# KNOT_v1_0_main.net
KiCad netlist of a schematic drawn in EAGLE
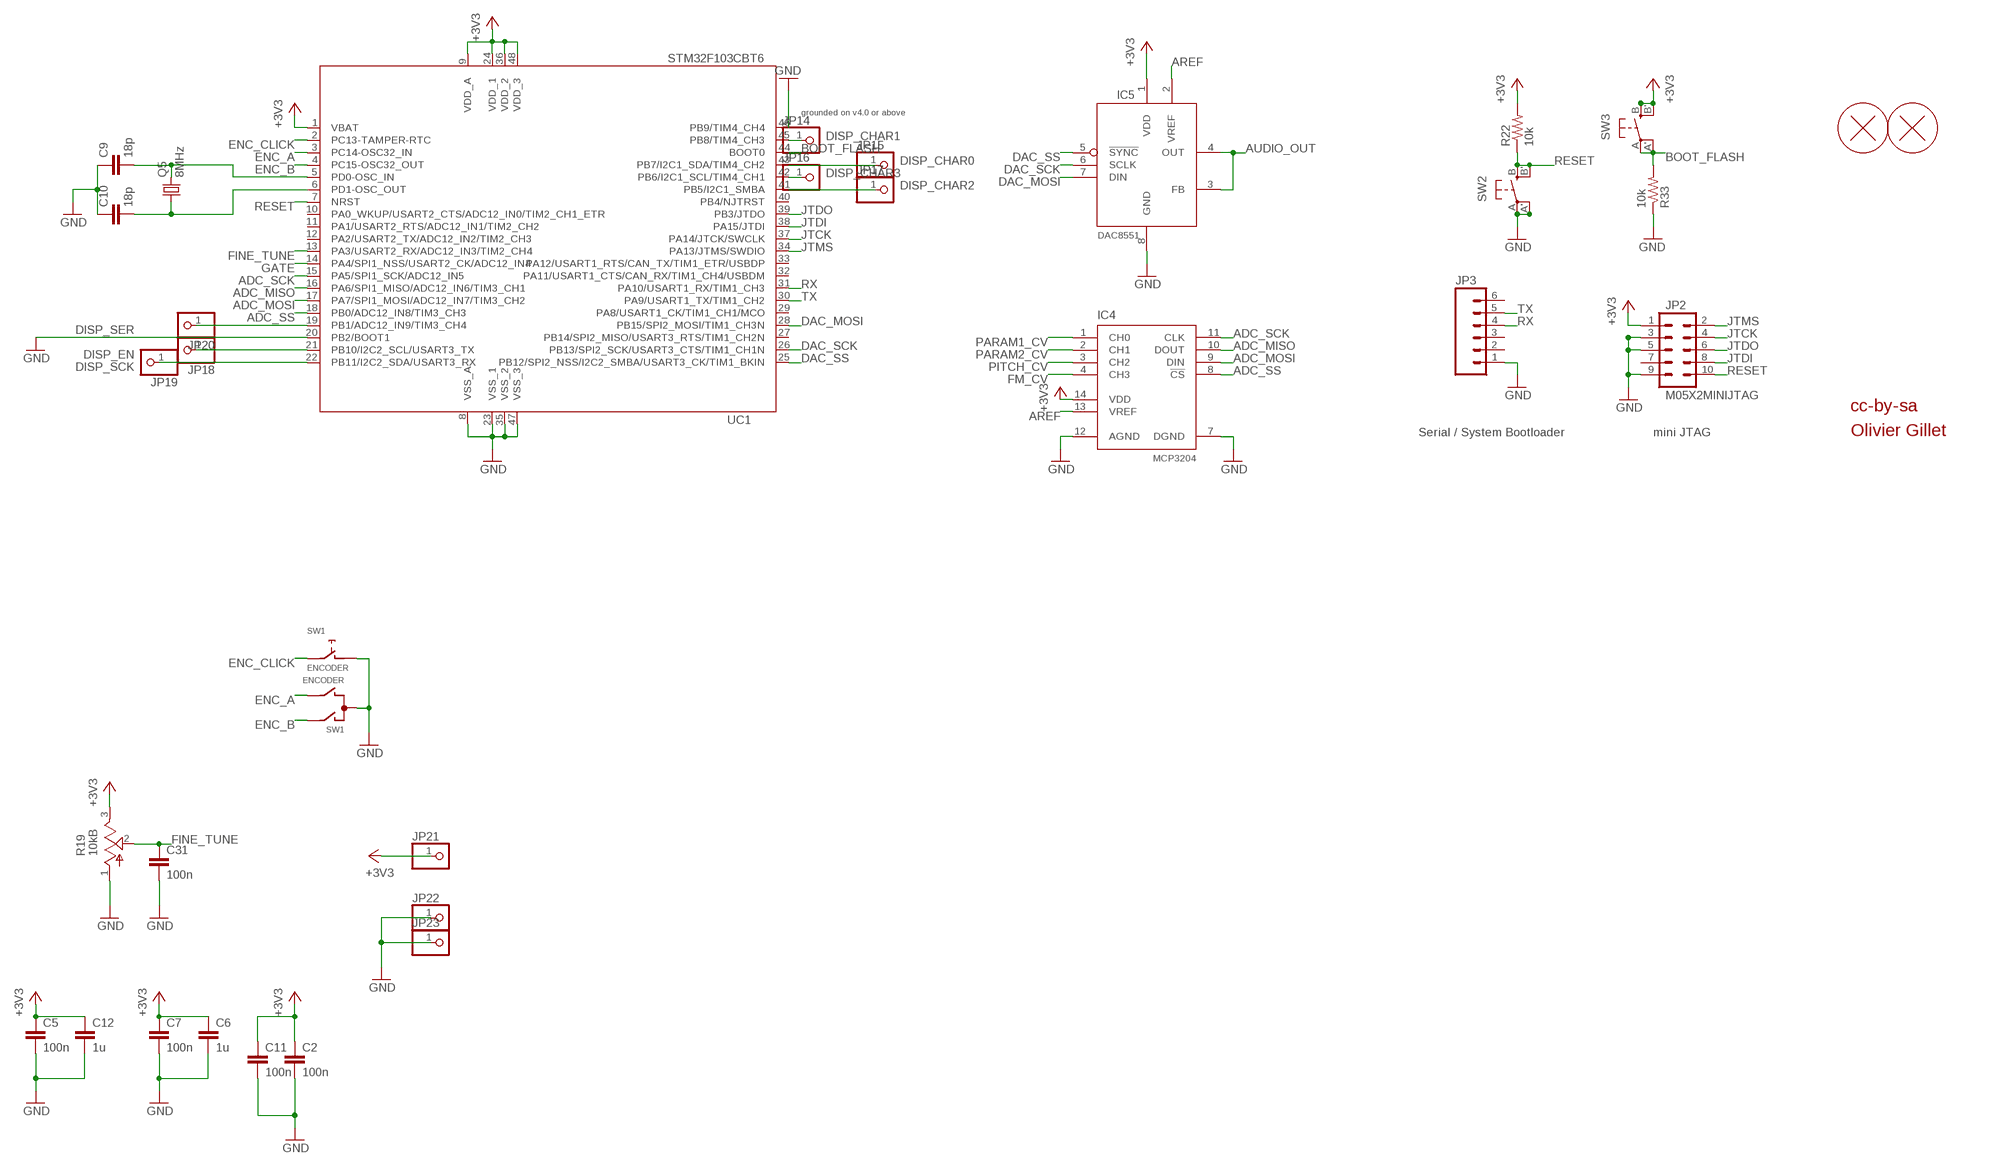
[diagram p0: schematic, sheet 1]
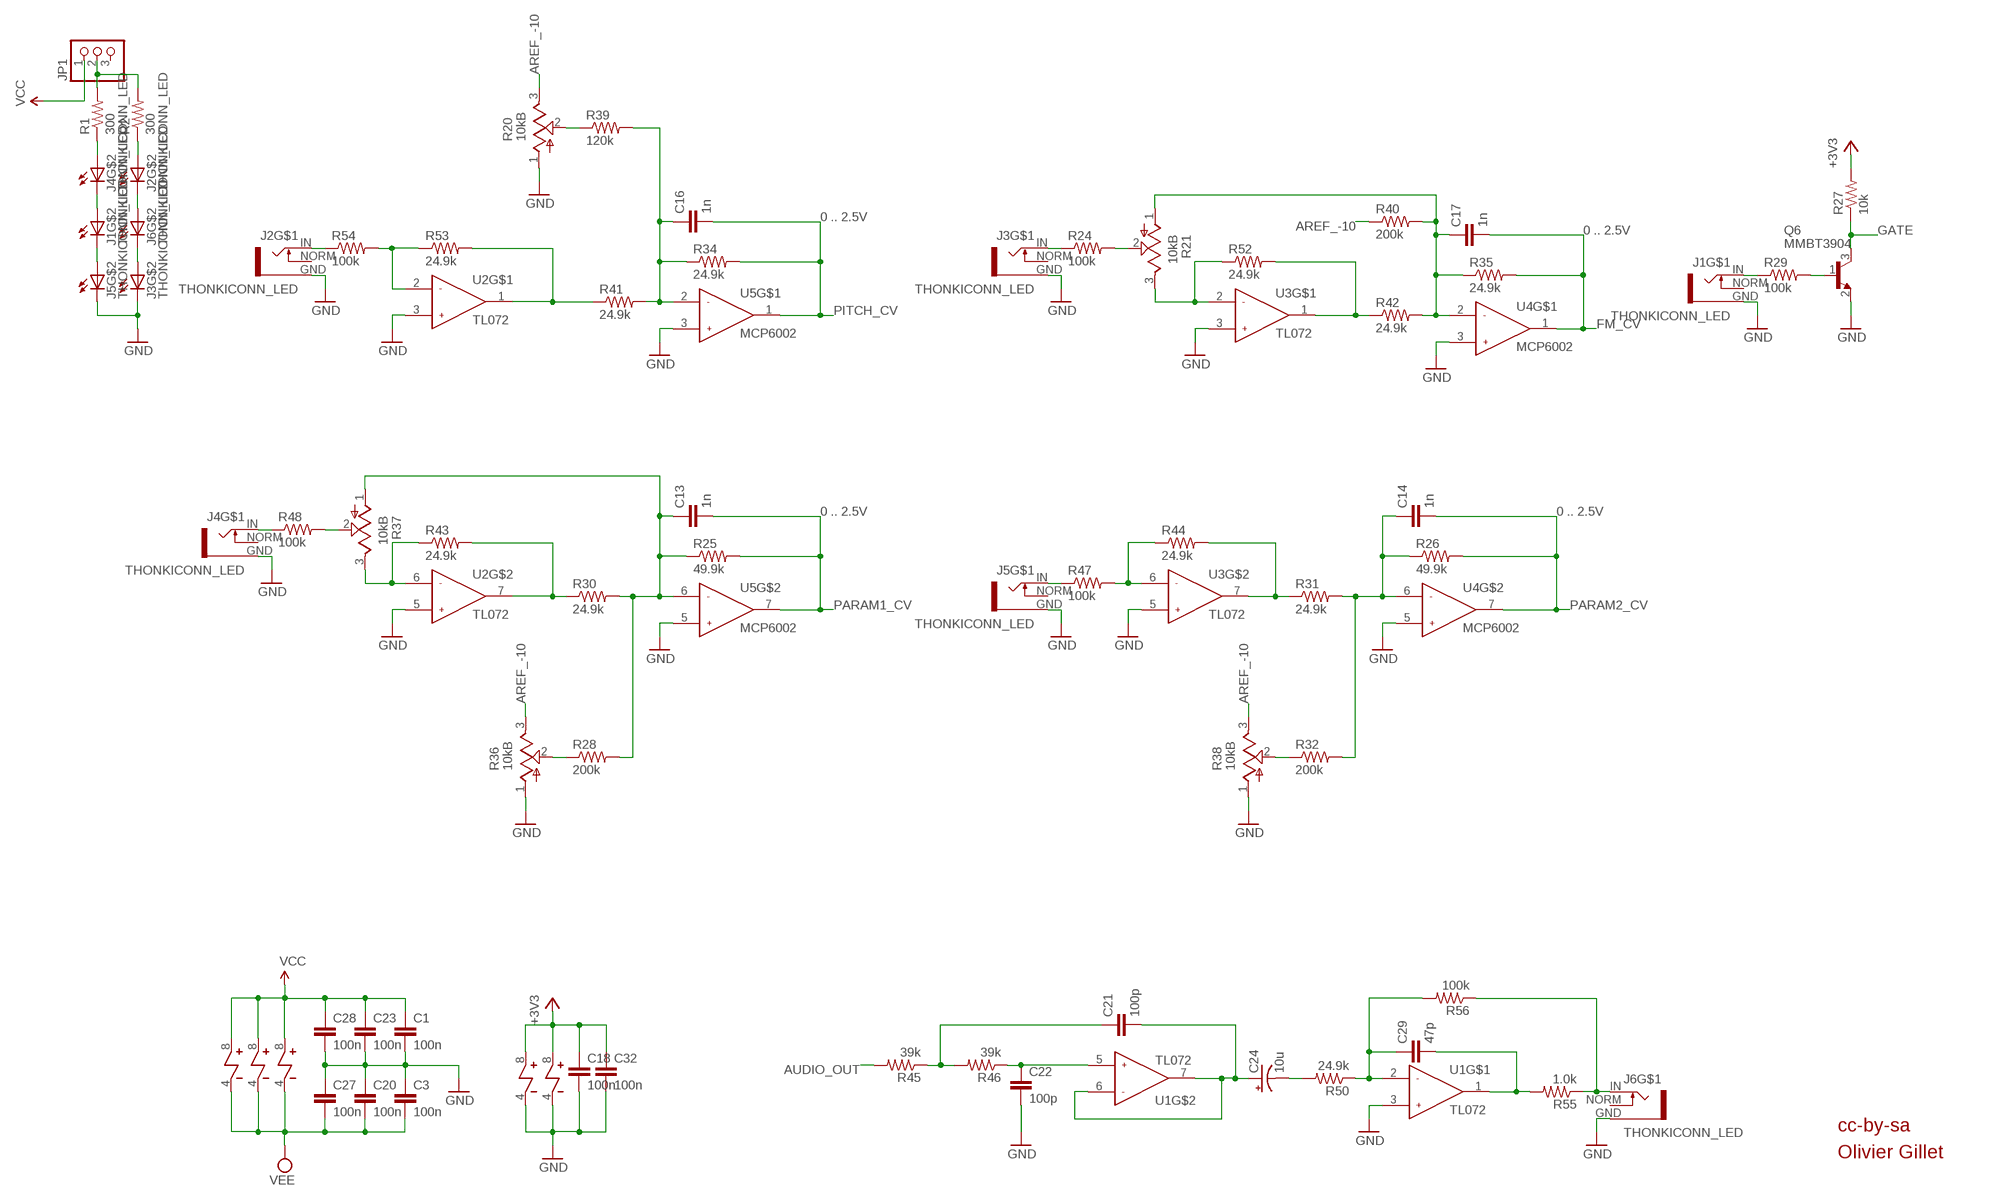
[diagram p1: schematic, sheet 2]
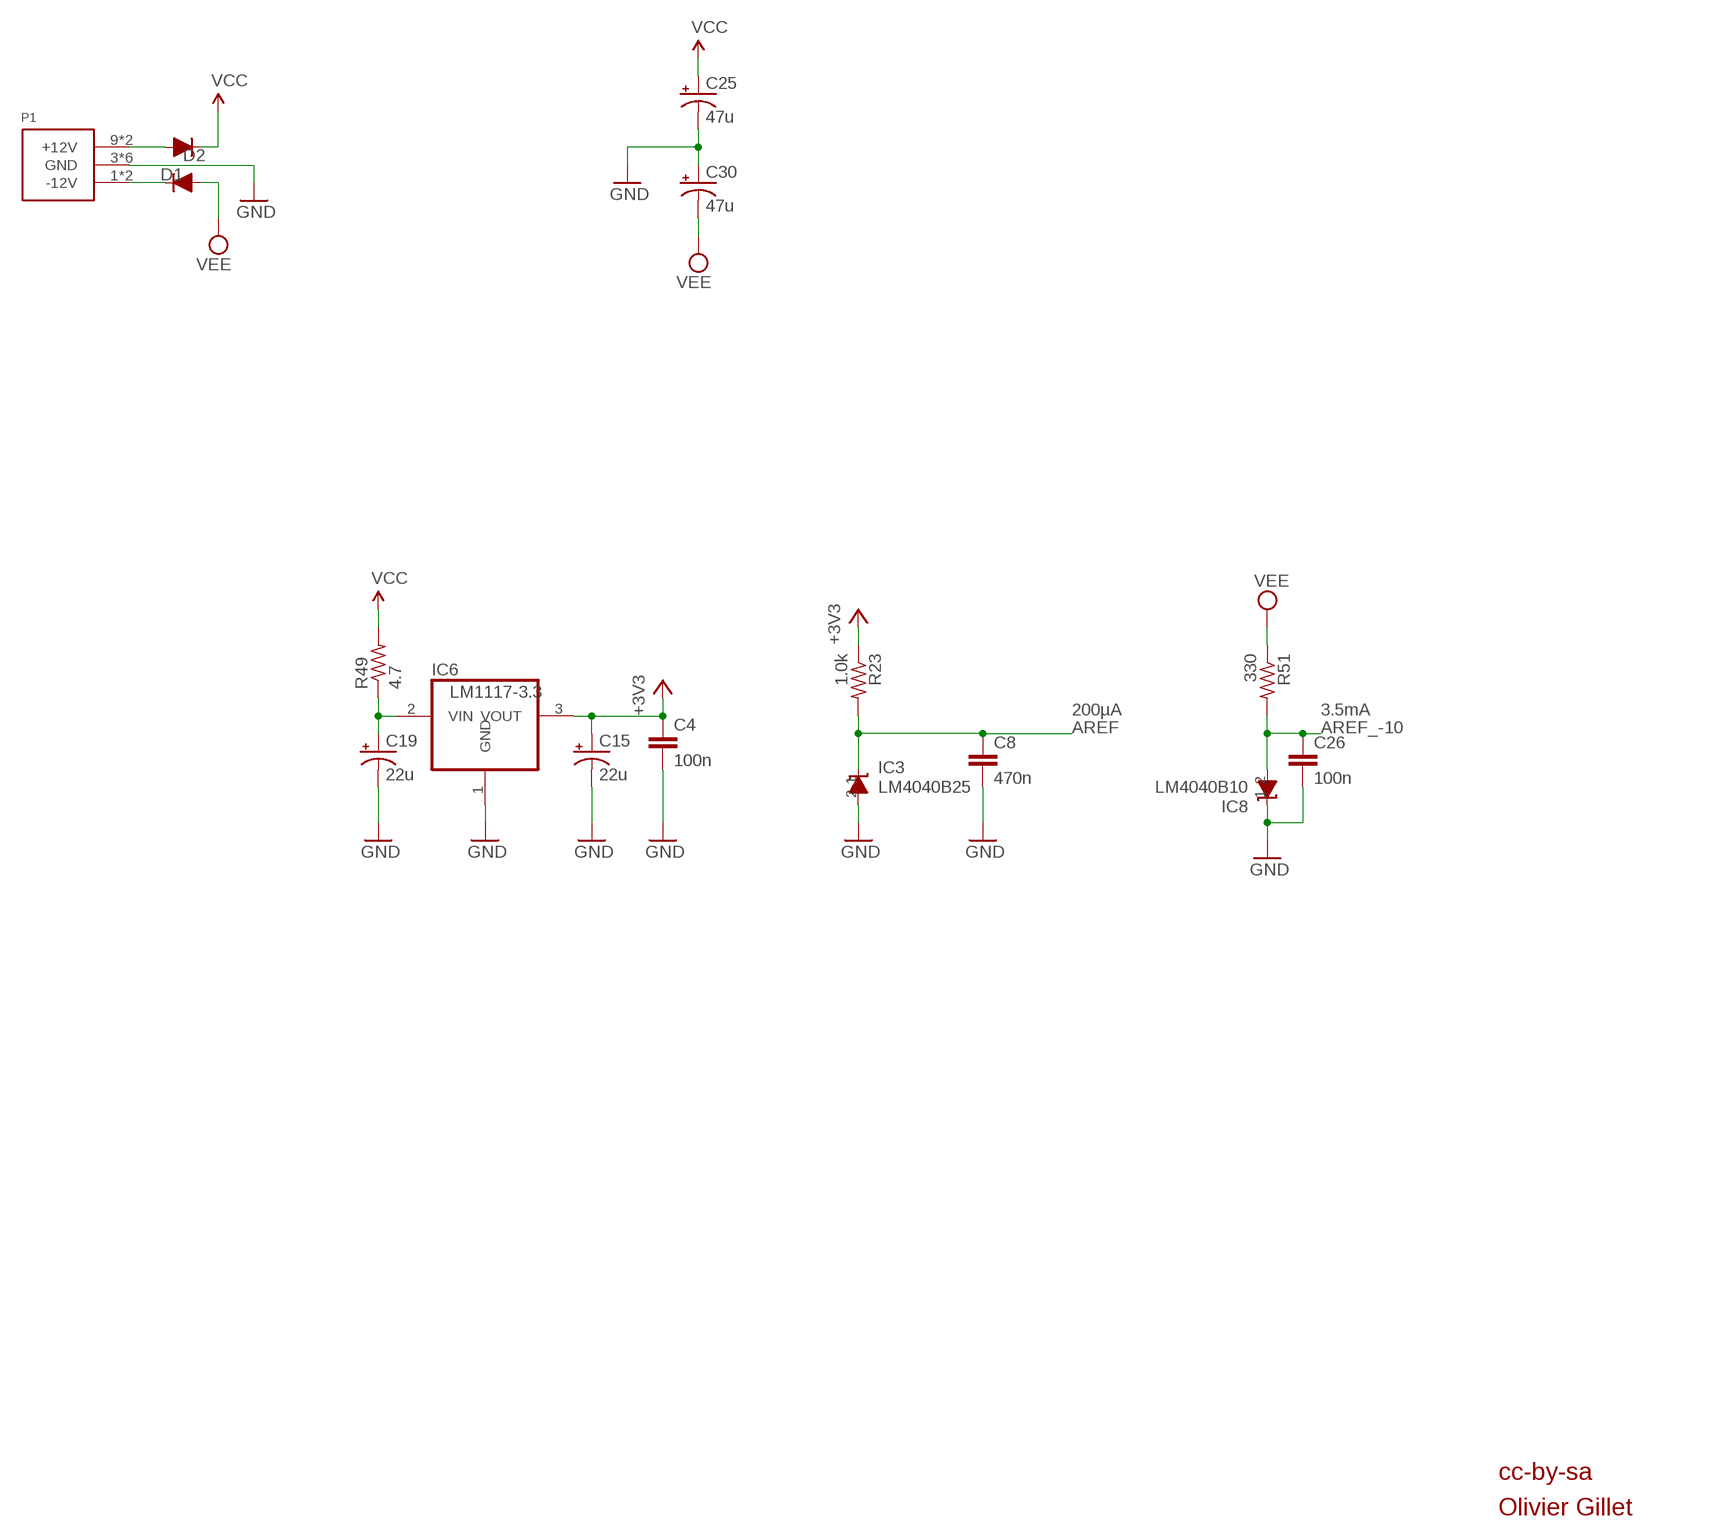
[diagram p2: schematic, sheet 3]

(export (version "E")
  (design (tool "Eeschema 10.0.6"))
  (components
    (comp (ref "C2")
      (value "100n")
      (footprint "eagle-import:RESISTOR_0603")
      (libsource (lib "eagle-import") (part "CAPACITOR"))
    )
    (comp (ref "C5")
      (value "100n")
      (footprint "eagle-import:RESISTOR_0603")
      (libsource (lib "eagle-import") (part "CAPACITOR"))
    )
    (comp (ref "C6")
      (value "1u")
      (footprint "eagle-import:RESISTOR_0603")
      (libsource (lib "eagle-import") (part "CAPACITOR"))
    )
    (comp (ref "C7")
      (value "100n")
      (footprint "eagle-import:RESISTOR_0603")
      (libsource (lib "eagle-import") (part "CAPACITOR"))
    )
    (comp (ref "C9")
      (value "18p")
      (footprint "eagle-import:RESISTOR_0603")
      (libsource (lib "eagle-import") (part "CAPACITOR"))
    )
    (comp (ref "C10")
      (value "18p")
      (footprint "eagle-import:RESISTOR_0603")
      (libsource (lib "eagle-import") (part "CAPACITOR"))
    )
    (comp (ref "C11")
      (value "100n")
      (footprint "eagle-import:RESISTOR_0603")
      (libsource (lib "eagle-import") (part "CAPACITOR"))
    )
    (comp (ref "C12")
      (value "1u")
      (footprint "eagle-import:RESISTOR_0603")
      (libsource (lib "eagle-import") (part "CAPACITOR"))
    )
    (comp (ref "C31")
      (value "100n")
      (footprint "eagle-import:RESISTOR_0603")
      (libsource (lib "eagle-import") (part "CAPACITOR"))
    )
    (comp (ref "H1")
      (value "PCB_SCREW")
      (footprint "eagle-import:PCB_SCREW")
      (libsource (lib "eagle-import") (part "PCB_SCREW"))
    )
    (comp (ref "H2")
      (value "PCB_SCREW")
      (footprint "eagle-import:PCB_SCREW")
      (libsource (lib "eagle-import") (part "PCB_SCREW"))
    )
    (comp (ref "IC4")
      (value "MCP3204")
      (footprint "eagle-import:SO14")
      (libsource (lib "eagle-import") (part "MCP3302"))
    )
    (comp (ref "IC5")
      (value "DAC8551")
      (footprint "eagle-import:MSOP-8")
      (libsource (lib "eagle-import") (part "DAC855X"))
    )
    (comp (ref "JP2")
      (value "M05X2MINIJTAG")
      (footprint "eagle-import:2X5-1.27")
      (libsource (lib "eagle-import") (part "M05X2MINIJTAG"))
    )
    (comp (ref "JP3")
      (value "M06SIP")
      (footprint "eagle-import:1X06")
      (libsource (lib "eagle-import") (part "M06SIP"))
    )
    (comp (ref "JP14")
      (value "PINHD-1X1")
      (footprint "eagle-import:1X01")
      (libsource (lib "eagle-import") (part "PINHD-1X1"))
    )
    (comp (ref "JP15")
      (value "PINHD-1X1")
      (footprint "eagle-import:1X01")
      (libsource (lib "eagle-import") (part "PINHD-1X1"))
    )
    (comp (ref "JP16")
      (value "PINHD-1X1")
      (footprint "eagle-import:1X01")
      (libsource (lib "eagle-import") (part "PINHD-1X1"))
    )
    (comp (ref "JP17")
      (value "PINHD-1X1")
      (footprint "eagle-import:1X01")
      (libsource (lib "eagle-import") (part "PINHD-1X1"))
    )
    (comp (ref "JP18")
      (value "PINHD-1X1")
      (footprint "eagle-import:1X01")
      (libsource (lib "eagle-import") (part "PINHD-1X1"))
    )
    (comp (ref "JP19")
      (value "PINHD-1X1")
      (footprint "eagle-import:1X01")
      (libsource (lib "eagle-import") (part "PINHD-1X1"))
    )
    (comp (ref "JP20")
      (value "PINHD-1X1")
      (footprint "eagle-import:1X01")
      (libsource (lib "eagle-import") (part "PINHD-1X1"))
    )
    (comp (ref "JP21")
      (value "PINHD-1X1")
      (footprint "eagle-import:1X01")
      (libsource (lib "eagle-import") (part "PINHD-1X1"))
    )
    (comp (ref "JP22")
      (value "PINHD-1X1")
      (footprint "eagle-import:1X01")
      (libsource (lib "eagle-import") (part "PINHD-1X1"))
    )
    (comp (ref "JP23")
      (value "PINHD-1X1")
      (footprint "eagle-import:1X01")
      (libsource (lib "eagle-import") (part "PINHD-1X1"))
    )
    (comp (ref "Q5")
      (value "8MHz")
      (footprint "eagle-import:HC49UP")
      (libsource (lib "eagle-import") (part "CRYSTAL"))
    )
    (comp (ref "R19")
      (value "10kB")
      (footprint "eagle-import:ALPS_POT_VERTICAL")
      (libsource (lib "eagle-import") (part "POT_VERTICAL"))
    )
    (comp (ref "R22")
      (value "10k")
      (footprint "eagle-import:RESISTOR_0603")
      (libsource (lib "eagle-import") (part "RESISTOR"))
    )
    (comp (ref "R33")
      (value "10k")
      (footprint "eagle-import:RESISTOR_0603")
      (libsource (lib "eagle-import") (part "RESISTOR"))
    )
    (comp (ref "SW1")
      (value "ENCODER")
      (footprint "eagle-import:ALPS_EC12E_SW")
      (fields (field (name "MPN") "EC12E2424407"))
      (libsource (lib "eagle-import") (part "ENCODER"))
    )
    (comp (ref "SW2")
      (value "EVQQ2")
      (footprint "eagle-import:EVQ-Q2")
      (libsource (lib "eagle-import") (part "EVQQ2"))
    )
    (comp (ref "SW3")
      (value "EVQQ2")
      (footprint "eagle-import:EVQ-Q2")
      (libsource (lib "eagle-import") (part "EVQQ2"))
    )
    (comp (ref "UC1")
      (value "STM32F103CBT6")
      (footprint "eagle-import:LQFP48")
      (libsource (lib "eagle-import") (part "STM32F103CB"))
    )
    (comp (ref "C1")
      (value "100n")
      (footprint "eagle-import:RESISTOR_0603")
      (libsource (lib "eagle-import") (part "CAPACITOR"))
    )
    (comp (ref "C3")
      (value "100n")
      (footprint "eagle-import:RESISTOR_0603")
      (libsource (lib "eagle-import") (part "CAPACITOR"))
    )
    (comp (ref "C13")
      (value "1n")
      (footprint "eagle-import:RESISTOR_0603")
      (libsource (lib "eagle-import") (part "CAPACITOR"))
    )
    (comp (ref "C14")
      (value "1n")
      (footprint "eagle-import:RESISTOR_0603")
      (libsource (lib "eagle-import") (part "CAPACITOR"))
    )
    (comp (ref "C16")
      (value "1n")
      (footprint "eagle-import:RESISTOR_0603")
      (libsource (lib "eagle-import") (part "CAPACITOR"))
    )
    (comp (ref "C17")
      (value "1n")
      (footprint "eagle-import:RESISTOR_0603")
      (libsource (lib "eagle-import") (part "CAPACITOR"))
    )
    (comp (ref "C18")
      (value "100n")
      (footprint "eagle-import:RESISTOR_0603")
      (libsource (lib "eagle-import") (part "CAPACITOR"))
    )
    (comp (ref "C20")
      (value "100n")
      (footprint "eagle-import:RESISTOR_0603")
      (libsource (lib "eagle-import") (part "CAPACITOR"))
    )
    (comp (ref "C21")
      (value "100p")
      (footprint "eagle-import:RESISTOR_0603")
      (libsource (lib "eagle-import") (part "CAPACITOR"))
    )
    (comp (ref "C22")
      (value "100p")
      (footprint "eagle-import:RESISTOR_0603")
      (libsource (lib "eagle-import") (part "CAPACITOR"))
    )
    (comp (ref "C23")
      (value "100n")
      (footprint "eagle-import:RESISTOR_0603")
      (libsource (lib "eagle-import") (part "CAPACITOR"))
    )
    (comp (ref "C24")
      (value "10u")
      (footprint "eagle-import:PANASONIC_B")
      (libsource (lib "eagle-import") (part "CAP_POL"))
    )
    (comp (ref "C27")
      (value "100n")
      (footprint "eagle-import:RESISTOR_0603")
      (libsource (lib "eagle-import") (part "CAPACITOR"))
    )
    (comp (ref "C28")
      (value "100n")
      (footprint "eagle-import:RESISTOR_0603")
      (libsource (lib "eagle-import") (part "CAPACITOR"))
    )
    (comp (ref "C29")
      (value "47p")
      (footprint "eagle-import:RESISTOR_0603")
      (libsource (lib "eagle-import") (part "CAPACITOR"))
    )
    (comp (ref "C32")
      (value "100n")
      (footprint "eagle-import:RESISTOR_0603")
      (libsource (lib "eagle-import") (part "CAPACITOR"))
    )
    (comp (ref "J1")
      (value "THONKICONN_LED")
      (footprint "eagle-import:LED_JACK")
      (libsource (lib "eagle-import") (part "THONKICONN_LED"))
    )
    (comp (ref "J2")
      (value "THONKICONN_LED")
      (footprint "eagle-import:LED_JACK")
      (libsource (lib "eagle-import") (part "THONKICONN_LED"))
    )
    (comp (ref "J3")
      (value "THONKICONN_LED")
      (footprint "eagle-import:LED_JACK")
      (libsource (lib "eagle-import") (part "THONKICONN_LED"))
    )
    (comp (ref "J4")
      (value "THONKICONN_LED")
      (footprint "eagle-import:LED_JACK")
      (libsource (lib "eagle-import") (part "THONKICONN_LED"))
    )
    (comp (ref "J5")
      (value "THONKICONN_LED")
      (footprint "eagle-import:LED_JACK")
      (libsource (lib "eagle-import") (part "THONKICONN_LED"))
    )
    (comp (ref "J6")
      (value "THONKICONN_LED")
      (footprint "eagle-import:LED_JACK")
      (libsource (lib "eagle-import") (part "THONKICONN_LED"))
    )
    (comp (ref "JP1")
      (value "PINHD-1X3")
      (footprint "eagle-import:1X03")
      (libsource (lib "eagle-import") (part "PINHD-1X3"))
    )
    (comp (ref "Q6")
      (value "MMBT3904")
      (footprint "eagle-import:SOT23")
      (libsource (lib "eagle-import") (part "MMBT3904SOT23"))
    )
    (comp (ref "R1")
      (value "300")
      (footprint "eagle-import:RESISTOR_0603")
      (libsource (lib "eagle-import") (part "RESISTOR"))
    )
    (comp (ref "R2")
      (value "300")
      (footprint "eagle-import:RESISTOR_0603")
      (libsource (lib "eagle-import") (part "RESISTOR"))
    )
    (comp (ref "R20")
      (value "10kB")
      (footprint "eagle-import:ALPS_POT_VERTICAL")
      (libsource (lib "eagle-import") (part "POT_VERTICAL"))
    )
    (comp (ref "R21")
      (value "10kB")
      (footprint "eagle-import:ALPS_POT_VERTICAL")
      (libsource (lib "eagle-import") (part "POT_VERTICAL"))
    )
    (comp (ref "R24")
      (value "100k")
      (footprint "eagle-import:RESISTOR_0603")
      (libsource (lib "eagle-import") (part "RESISTOR"))
    )
    (comp (ref "R25")
      (value "49.9k")
      (footprint "eagle-import:RESISTOR_0603")
      (libsource (lib "eagle-import") (part "RESISTOR"))
    )
    (comp (ref "R26")
      (value "49.9k")
      (footprint "eagle-import:RESISTOR_0603")
      (libsource (lib "eagle-import") (part "RESISTOR"))
    )
    (comp (ref "R27")
      (value "10k")
      (footprint "eagle-import:RESISTOR_0603")
      (libsource (lib "eagle-import") (part "RESISTOR"))
    )
    (comp (ref "R28")
      (value "200k")
      (footprint "eagle-import:RESISTOR_0603")
      (libsource (lib "eagle-import") (part "RESISTOR"))
    )
    (comp (ref "R29")
      (value "100k")
      (footprint "eagle-import:RESISTOR_0603")
      (libsource (lib "eagle-import") (part "RESISTOR"))
    )
    (comp (ref "R30")
      (value "24.9k")
      (footprint "eagle-import:RESISTOR_0603")
      (libsource (lib "eagle-import") (part "RESISTOR"))
    )
    (comp (ref "R31")
      (value "24.9k")
      (footprint "eagle-import:RESISTOR_0603")
      (libsource (lib "eagle-import") (part "RESISTOR"))
    )
    (comp (ref "R32")
      (value "200k")
      (footprint "eagle-import:RESISTOR_0603")
      (libsource (lib "eagle-import") (part "RESISTOR"))
    )
    (comp (ref "R34")
      (value "24.9k")
      (footprint "eagle-import:RESISTOR_0603")
      (libsource (lib "eagle-import") (part "RESISTOR"))
    )
    (comp (ref "R35")
      (value "24.9k")
      (footprint "eagle-import:RESISTOR_0603")
      (libsource (lib "eagle-import") (part "RESISTOR"))
    )
    (comp (ref "R36")
      (value "10kB")
      (footprint "eagle-import:ALPS_POT_VERTICAL")
      (libsource (lib "eagle-import") (part "POT_VERTICAL"))
    )
    (comp (ref "R37")
      (value "10kB")
      (footprint "eagle-import:ALPS_POT_VERTICAL")
      (libsource (lib "eagle-import") (part "POT_VERTICAL"))
    )
    (comp (ref "R38")
      (value "10kB")
      (footprint "eagle-import:ALPS_POT_VERTICAL")
      (libsource (lib "eagle-import") (part "POT_VERTICAL"))
    )
    (comp (ref "R39")
      (value "120k")
      (footprint "eagle-import:RESISTOR_0603")
      (libsource (lib "eagle-import") (part "RESISTOR"))
    )
    (comp (ref "R40")
      (value "200k")
      (footprint "eagle-import:RESISTOR_0603")
      (libsource (lib "eagle-import") (part "RESISTOR"))
    )
    (comp (ref "R41")
      (value "24.9k")
      (footprint "eagle-import:RESISTOR_0603")
      (libsource (lib "eagle-import") (part "RESISTOR"))
    )
    (comp (ref "R42")
      (value "24.9k")
      (footprint "eagle-import:RESISTOR_0603")
      (libsource (lib "eagle-import") (part "RESISTOR"))
    )
    (comp (ref "R43")
      (value "24.9k")
      (footprint "eagle-import:RESISTOR_0603")
      (libsource (lib "eagle-import") (part "RESISTOR"))
    )
    (comp (ref "R44")
      (value "24.9k")
      (footprint "eagle-import:RESISTOR_0603")
      (libsource (lib "eagle-import") (part "RESISTOR"))
    )
    (comp (ref "R45")
      (value "39k")
      (footprint "eagle-import:RESISTOR_0603")
      (libsource (lib "eagle-import") (part "RESISTOR"))
    )
    (comp (ref "R46")
      (value "39k")
      (footprint "eagle-import:RESISTOR_0603")
      (libsource (lib "eagle-import") (part "RESISTOR"))
    )
    (comp (ref "R47")
      (value "100k")
      (footprint "eagle-import:RESISTOR_0603")
      (libsource (lib "eagle-import") (part "RESISTOR"))
    )
    (comp (ref "R48")
      (value "100k")
      (footprint "eagle-import:RESISTOR_0603")
      (libsource (lib "eagle-import") (part "RESISTOR"))
    )
    (comp (ref "R50")
      (value "24.9k")
      (footprint "eagle-import:RESISTOR_0603")
      (libsource (lib "eagle-import") (part "RESISTOR"))
    )
    (comp (ref "R52")
      (value "24.9k")
      (footprint "eagle-import:RESISTOR_0603")
      (libsource (lib "eagle-import") (part "RESISTOR"))
    )
    (comp (ref "R53")
      (value "24.9k")
      (footprint "eagle-import:RESISTOR_0603")
      (libsource (lib "eagle-import") (part "RESISTOR"))
    )
    (comp (ref "R54")
      (value "100k")
      (footprint "eagle-import:RESISTOR_0603")
      (libsource (lib "eagle-import") (part "RESISTOR"))
    )
    (comp (ref "R55")
      (value "1.0k")
      (footprint "eagle-import:RESISTOR_0603")
      (libsource (lib "eagle-import") (part "RESISTOR"))
    )
    (comp (ref "R56")
      (value "100k")
      (footprint "eagle-import:RESISTOR_0603")
      (libsource (lib "eagle-import") (part "RESISTOR"))
    )
    (comp (ref "U1")
      (value "TL072")
      (footprint "eagle-import:SOIC8")
      (libsource (lib "eagle-import") (part "OPAMP_DUAL"))
    )
    (comp (ref "U2")
      (value "TL072")
      (footprint "eagle-import:SOIC8")
      (libsource (lib "eagle-import") (part "OPAMP_DUAL"))
    )
    (comp (ref "U3")
      (value "TL072")
      (footprint "eagle-import:SOIC8")
      (libsource (lib "eagle-import") (part "OPAMP_DUAL"))
    )
    (comp (ref "U4")
      (value "MCP6002")
      (footprint "eagle-import:SOIC8")
      (libsource (lib "eagle-import") (part "OPAMP_DUAL"))
    )
    (comp (ref "U5")
      (value "MCP6002")
      (footprint "eagle-import:SOIC8")
      (libsource (lib "eagle-import") (part "OPAMP_DUAL"))
    )
    (comp (ref "C4")
      (value "100n")
      (footprint "eagle-import:RESISTOR_0603")
      (libsource (lib "eagle-import") (part "CAPACITOR"))
    )
    (comp (ref "C8")
      (value "470n")
      (footprint "eagle-import:RESISTOR_0603")
      (libsource (lib "eagle-import") (part "CAPACITOR"))
    )
    (comp (ref "C15")
      (value "22u")
      (footprint "eagle-import:PANASONIC_D")
      (libsource (lib "eagle-import") (part "CAP_POLD"))
    )
    (comp (ref "C19")
      (value "22u")
      (footprint "eagle-import:PANASONIC_D")
      (libsource (lib "eagle-import") (part "CAP_POLD"))
    )
    (comp (ref "C25")
      (value "47u")
      (footprint "eagle-import:PANASONIC_D")
      (libsource (lib "eagle-import") (part "CAP_POLD"))
    )
    (comp (ref "C26")
      (value "100n")
      (footprint "eagle-import:RESISTOR_0603")
      (libsource (lib "eagle-import") (part "CAPACITOR"))
    )
    (comp (ref "C30")
      (value "47u")
      (footprint "eagle-import:PANASONIC_D")
      (libsource (lib "eagle-import") (part "CAP_POLD"))
    )
    (comp (ref "D1")
      (value "1N5819HW")
      (footprint "eagle-import:SOD123")
      (libsource (lib "eagle-import") (part "DIODE"))
    )
    (comp (ref "D2")
      (value "1N5819HW")
      (footprint "eagle-import:SOD123")
      (libsource (lib "eagle-import") (part "DIODE"))
    )
    (comp (ref "IC3")
      (value "LM4040B25")
      (footprint "eagle-import:SOT23")
      (libsource (lib "eagle-import") (part "LM4040SOT23"))
    )
    (comp (ref "IC6")
      (value "LM1117-3.3")
      (footprint "eagle-import:TO252")
      (libsource (lib "eagle-import") (part "REG1117T"))
    )
    (comp (ref "IC8")
      (value "LM4040B10")
      (footprint "eagle-import:SOT23")
      (libsource (lib "eagle-import") (part "LM4040SOT23"))
    )
    (comp (ref "P1")
      (value "POWER_SIMPLE10")
      (footprint "eagle-import:POWER_10")
      (libsource (lib "eagle-import") (part "POWER_SIMPLE10"))
    )
    (comp (ref "R23")
      (value "1.0k")
      (footprint "eagle-import:RESISTOR_0603")
      (libsource (lib "eagle-import") (part "RESISTOR"))
    )
    (comp (ref "R49")
      (value "4.7")
      (footprint "eagle-import:RESISTOR_0603")
      (libsource (lib "eagle-import") (part "RESISTOR"))
    )
    (comp (ref "R51")
      (value "330")
      (footprint "eagle-import:RESISTOR_0603")
      (libsource (lib "eagle-import") (part "RESISTOR"))
    )
  )
  (nets
    (net (code "1") (name "+3V3") (class "Default")
      (node (ref "C11") (pin "1") (pinfunction "1_1") (pintype "passive"))
      (node (ref "C12") (pin "1") (pinfunction "1_1") (pintype "passive"))
      (node (ref "C15") (pin "+") (pinfunction "+_+") (pintype "passive"))
      (node (ref "C18") (pin "1") (pinfunction "1_1") (pintype "passive"))
      (node (ref "C2") (pin "1") (pinfunction "1_1") (pintype "passive"))
      (node (ref "C32") (pin "1") (pinfunction "1_1") (pintype "passive"))
      (node (ref "C4") (pin "1") (pinfunction "1_1") (pintype "passive"))
      (node (ref "C5") (pin "1") (pinfunction "1_1") (pintype "passive"))
      (node (ref "C6") (pin "1") (pinfunction "1_1") (pintype "passive"))
      (node (ref "C7") (pin "1") (pinfunction "1_1") (pintype "passive"))
      (node (ref "IC4") (pin "14") (pinfunction "VDD_14") (pintype "bidirectional"))
      (node (ref "IC5") (pin "1") (pinfunction "VDD_1") (pintype "power_in"))
      (node (ref "IC6") (pin "3") (pinfunction "VOUT_3") (pintype "output"))
      (node (ref "JP2") (pin "1") (pinfunction "1_1") (pintype "passive"))
      (node (ref "JP21") (pin "1") (pinfunction "1_1") (pintype "passive"))
      (node (ref "R19") (pin "3") (pinfunction "B_3") (pintype "passive"))
      (node (ref "R22") (pin "2") (pinfunction "2_2") (pintype "passive"))
      (node (ref "R23") (pin "1") (pinfunction "1_1") (pintype "passive"))
      (node (ref "R27") (pin "2") (pinfunction "2_2") (pintype "passive"))
      (node (ref "SW3") (pin "B") (pinfunction "S_B") (pintype "passive"))
      (node (ref "SW3") (pin "B'") (pinfunction "S1_B'") (pintype "passive"))
      (node (ref "U4") (pin "8") (pinfunction "P$1_8") (pintype "bidirectional"))
      (node (ref "U5") (pin "8") (pinfunction "P$1_8") (pintype "bidirectional"))
      (node (ref "UC1") (pin "1") (pinfunction "VBAT_1") (pintype "power_in"))
      (node (ref "UC1") (pin "24") (pinfunction "VDD_1_24") (pintype "power_in"))
      (node (ref "UC1") (pin "36") (pinfunction "VDD_2_36") (pintype "power_in"))
      (node (ref "UC1") (pin "48") (pinfunction "VDD_3_48") (pintype "power_in"))
      (node (ref "UC1") (pin "9") (pinfunction "VDD_A_9") (pintype "power_in"))
    )
    (net (code "2") (name "ADC_MISO") (class "Default")
      (node (ref "IC4") (pin "10") (pinfunction "DOUT_10") (pintype "bidirectional"))
      (node (ref "UC1") (pin "16") (pinfunction "PA6/SPI1_MISO/ADC12_IN6/TIM3_CH1_16") (pintype "bidirectional"))
    )
    (net (code "3") (name "ADC_MOSI") (class "Default")
      (node (ref "IC4") (pin "9") (pinfunction "DIN_9") (pintype "bidirectional"))
      (node (ref "UC1") (pin "17") (pinfunction "PA7/SPI1_MOSI/ADC12_IN7/TIM3_CH2_17") (pintype "bidirectional"))
    )
    (net (code "4") (name "ADC_SCK") (class "Default")
      (node (ref "IC4") (pin "11") (pinfunction "CLK_11") (pintype "bidirectional"))
      (node (ref "UC1") (pin "15") (pinfunction "PA5/SPI1_SCK/ADC12_IN5_15") (pintype "bidirectional"))
    )
    (net (code "5") (name "ADC_SS") (class "Default")
      (node (ref "IC4") (pin "8") (pinfunction "~{CS}_8") (pintype "bidirectional"))
      (node (ref "UC1") (pin "18") (pinfunction "PB0/ADC12_IN8/TIM3_CH3_18") (pintype "bidirectional"))
    )
    (net (code "6") (name "AREF") (class "Default")
      (node (ref "C8") (pin "1") (pinfunction "1_1") (pintype "passive"))
      (node (ref "IC3") (pin "1") (pinfunction "C_1") (pintype "passive"))
      (node (ref "IC4") (pin "13") (pinfunction "VREF_13") (pintype "bidirectional"))
      (node (ref "IC5") (pin "2") (pinfunction "VREF_2") (pintype "power_in"))
      (node (ref "R23") (pin "2") (pinfunction "2_2") (pintype "passive"))
    )
    (net (code "7") (name "AREF_-10") (class "Default")
      (node (ref "C26") (pin "1") (pinfunction "1_1") (pintype "passive"))
      (node (ref "IC8") (pin "2") (pinfunction "A_2") (pintype "passive"))
      (node (ref "R20") (pin "3") (pinfunction "B_3") (pintype "passive"))
      (node (ref "R36") (pin "3") (pinfunction "B_3") (pintype "passive"))
      (node (ref "R38") (pin "3") (pinfunction "B_3") (pintype "passive"))
      (node (ref "R40") (pin "1") (pinfunction "1_1") (pintype "passive"))
      (node (ref "R51") (pin "2") (pinfunction "2_2") (pintype "passive"))
    )
    (net (code "8") (name "AUDIO_OUT") (class "Default")
      (node (ref "IC5") (pin "3") (pinfunction "FB_3") (pintype "input"))
      (node (ref "IC5") (pin "4") (pinfunction "OUT_4") (pintype "output"))
      (node (ref "R45") (pin "2") (pinfunction "2_2") (pintype "passive"))
    )
    (net (code "9") (name "BOOT_FLASH") (class "Default")
      (node (ref "R33") (pin "2") (pinfunction "2_2") (pintype "passive"))
      (node (ref "SW3") (pin "A") (pinfunction "P_A") (pintype "passive"))
      (node (ref "SW3") (pin "A'") (pinfunction "P1_A'") (pintype "passive"))
      (node (ref "UC1") (pin "44") (pinfunction "BOOT0_44") (pintype "input"))
    )
    (net (code "10") (name "DAC_MOSI") (class "Default")
      (node (ref "IC5") (pin "7") (pinfunction "DIN_7") (pintype "bidirectional"))
      (node (ref "UC1") (pin "28") (pinfunction "PB15/SPI2_MOSI/TIM1_CH3N_28") (pintype "input"))
    )
    (net (code "11") (name "DAC_SCK") (class "Default")
      (node (ref "IC5") (pin "6") (pinfunction "SCLK_6") (pintype "bidirectional"))
      (node (ref "UC1") (pin "26") (pinfunction "PB13/SPI2_SCK/USART3_CTS/TIM1_CH1N_26") (pintype "input"))
    )
    (net (code "12") (name "DAC_SS") (class "Default")
      (node (ref "IC5") (pin "5") (pinfunction "~{SYNC}_5") (pintype "bidirectional"))
      (node (ref "UC1") (pin "25") (pinfunction "PB12/SPI2_NSS/I2C2_SMBA/USART3_CK/TIM1_BKIN_25") (pintype "input"))
    )
    (net (code "13") (name "DISP_CHAR0") (class "Default")
      (node (ref "JP15") (pin "1") (pinfunction "1_1") (pintype "passive"))
      (node (ref "UC1") (pin "43") (pinfunction "PB7/I2C1_SDA/TIM4_CH2_43") (pintype "bidirectional"))
    )
    (net (code "14") (name "DISP_CHAR1") (class "Default")
      (node (ref "JP14") (pin "1") (pinfunction "1_1") (pintype "passive"))
      (node (ref "UC1") (pin "45") (pinfunction "PB8/TIM4_CH3_45") (pintype "bidirectional"))
    )
    (net (code "15") (name "DISP_CHAR2") (class "Default")
      (node (ref "JP17") (pin "1") (pinfunction "1_1") (pintype "passive"))
      (node (ref "UC1") (pin "41") (pinfunction "PB5/I2C1_SMBA_41") (pintype "input"))
    )
    (net (code "16") (name "DISP_CHAR3") (class "Default")
      (node (ref "JP16") (pin "1") (pinfunction "1_1") (pintype "passive"))
      (node (ref "UC1") (pin "42") (pinfunction "PB6/I2C1_SCL/TIM4_CH1_42") (pintype "input"))
    )
    (net (code "17") (name "DISP_EN") (class "Default")
      (node (ref "JP18") (pin "1") (pinfunction "1_1") (pintype "passive"))
      (node (ref "UC1") (pin "21") (pinfunction "PB10/I2C2_SCL/USART3_TX_21") (pintype "input"))
    )
    (net (code "18") (name "DISP_SCK") (class "Default")
      (node (ref "JP19") (pin "1") (pinfunction "1_1") (pintype "passive"))
      (node (ref "UC1") (pin "22") (pinfunction "PB11/I2C2_SDA/USART3_RX_22") (pintype "input"))
    )
    (net (code "19") (name "DISP_SER") (class "Default")
      (node (ref "JP20") (pin "1") (pinfunction "1_1") (pintype "passive"))
      (node (ref "UC1") (pin "19") (pinfunction "PB1/ADC12_IN9/TIM3_CH4_19") (pintype "bidirectional"))
    )
    (net (code "20") (name "ENC_A") (class "Default")
      (node (ref "SW1") (pin "B") (pinfunction "B_B") (pintype "passive"))
      (node (ref "UC1") (pin "3") (pinfunction "PC14-OSC32_IN_3") (pintype "input"))
    )
    (net (code "21") (name "ENC_B") (class "Default")
      (node (ref "SW1") (pin "A") (pinfunction "A_A") (pintype "passive"))
      (node (ref "UC1") (pin "4") (pinfunction "PC15-OSC32_OUT_4") (pintype "input"))
    )
    (net (code "22") (name "ENC_CLICK") (class "Default")
      (node (ref "SW1") (pin "E") (pinfunction "2_E") (pintype "passive"))
      (node (ref "UC1") (pin "2") (pinfunction "PC13-TAMPER-RTC_2") (pintype "input"))
    )
    (net (code "23") (name "FINE_TUNE") (class "Default")
      (node (ref "C31") (pin "1") (pinfunction "1_1") (pintype "passive"))
      (node (ref "R19") (pin "2") (pinfunction "W_2") (pintype "passive"))
      (node (ref "UC1") (pin "13") (pinfunction "PA3/USART2_RX/ADC12_IN3/TIM2_CH4_13") (pintype "bidirectional"))
    )
    (net (code "24") (name "FM_CV") (class "Default")
      (node (ref "C17") (pin "2") (pinfunction "2_2") (pintype "passive"))
      (node (ref "IC4") (pin "4") (pinfunction "CH3_4") (pintype "bidirectional"))
      (node (ref "R35") (pin "2") (pinfunction "2_2") (pintype "passive"))
      (node (ref "U4") (pin "1") (pinfunction "P$3_1") (pintype "bidirectional"))
    )
    (net (code "25") (name "GATE") (class "Default")
      (node (ref "Q6") (pin "3") (pinfunction "C_3") (pintype "passive"))
      (node (ref "R27") (pin "1") (pinfunction "1_1") (pintype "passive"))
      (node (ref "UC1") (pin "14") (pinfunction "PA4/SPI1_NSS/USART2_CK/ADC12_IN4_14") (pintype "bidirectional"))
    )
    (net (code "26") (name "GND") (class "Default")
      (node (ref "C1") (pin "2") (pinfunction "2_2") (pintype "passive"))
      (node (ref "C10") (pin "1") (pinfunction "1_1") (pintype "passive"))
      (node (ref "C11") (pin "2") (pinfunction "2_2") (pintype "passive"))
      (node (ref "C12") (pin "2") (pinfunction "2_2") (pintype "passive"))
      (node (ref "C15") (pin "-") (pinfunction "-_-") (pintype "passive"))
      (node (ref "C18") (pin "2") (pinfunction "2_2") (pintype "passive"))
      (node (ref "C19") (pin "-") (pinfunction "-_-") (pintype "passive"))
      (node (ref "C2") (pin "2") (pinfunction "2_2") (pintype "passive"))
      (node (ref "C20") (pin "1") (pinfunction "1_1") (pintype "passive"))
      (node (ref "C22") (pin "2") (pinfunction "2_2") (pintype "passive"))
      (node (ref "C23") (pin "2") (pinfunction "2_2") (pintype "passive"))
      (node (ref "C25") (pin "-") (pinfunction "-_-") (pintype "passive"))
      (node (ref "C26") (pin "2") (pinfunction "2_2") (pintype "passive"))
      (node (ref "C27") (pin "1") (pinfunction "1_1") (pintype "passive"))
      (node (ref "C28") (pin "2") (pinfunction "2_2") (pintype "passive"))
      (node (ref "C3") (pin "1") (pinfunction "1_1") (pintype "passive"))
      (node (ref "C30") (pin "+") (pinfunction "+_+") (pintype "passive"))
      (node (ref "C31") (pin "2") (pinfunction "2_2") (pintype "passive"))
      (node (ref "C32") (pin "2") (pinfunction "2_2") (pintype "passive"))
      (node (ref "C4") (pin "2") (pinfunction "2_2") (pintype "passive"))
      (node (ref "C5") (pin "2") (pinfunction "2_2") (pintype "passive"))
      (node (ref "C6") (pin "2") (pinfunction "2_2") (pintype "passive"))
      (node (ref "C7") (pin "2") (pinfunction "2_2") (pintype "passive"))
      (node (ref "C8") (pin "2") (pinfunction "2_2") (pintype "passive"))
      (node (ref "C9") (pin "1") (pinfunction "1_1") (pintype "passive"))
      (node (ref "IC3") (pin "2") (pinfunction "A_2") (pintype "passive"))
      (node (ref "IC4") (pin "12") (pinfunction "AGND_12") (pintype "bidirectional"))
      (node (ref "IC4") (pin "7") (pinfunction "DGND_7") (pintype "bidirectional"))
      (node (ref "IC5") (pin "8") (pinfunction "GND_8") (pintype "power_in"))
      (node (ref "IC6") (pin "1") (pinfunction "GND_1") (pintype "power_in"))
      (node (ref "IC8") (pin "1") (pinfunction "C_1") (pintype "passive"))
      (node (ref "J1") (pin "GND") (pinfunction "GND_GND") (pintype "passive"))
      (node (ref "J2") (pin "GND") (pinfunction "GND_GND") (pintype "passive"))
      (node (ref "J3") (pin "C") (pinfunction "C_C") (pintype "passive"))
      (node (ref "J3") (pin "GND") (pinfunction "GND_GND") (pintype "passive"))
      (node (ref "J4") (pin "GND") (pinfunction "GND_GND") (pintype "passive"))
      (node (ref "J5") (pin "C") (pinfunction "C_C") (pintype "passive"))
      (node (ref "J5") (pin "GND") (pinfunction "GND_GND") (pintype "passive"))
      (node (ref "J6") (pin "GND") (pinfunction "GND_GND") (pintype "passive"))
      (node (ref "JP2") (pin "3") (pinfunction "3_3") (pintype "passive"))
      (node (ref "JP2") (pin "5") (pinfunction "5_5") (pintype "passive"))
      (node (ref "JP2") (pin "9") (pinfunction "9_9") (pintype "passive"))
      (node (ref "JP22") (pin "1") (pinfunction "1_1") (pintype "passive"))
      (node (ref "JP23") (pin "1") (pinfunction "1_1") (pintype "passive"))
      (node (ref "JP3") (pin "1") (pinfunction "1_1") (pintype "passive"))
      (node (ref "P1") (pin "3") (pinfunction "GND_3") (pintype "bidirectional"))
      (node (ref "P1") (pin "4") (pinfunction "GND_4") (pintype "bidirectional"))
      (node (ref "P1") (pin "5") (pinfunction "GND_5") (pintype "bidirectional"))
      (node (ref "P1") (pin "6") (pinfunction "GND_6") (pintype "bidirectional"))
      (node (ref "P1") (pin "7") (pinfunction "GND_7") (pintype "bidirectional"))
      (node (ref "P1") (pin "8") (pinfunction "GND_8") (pintype "bidirectional"))
      (node (ref "Q6") (pin "2") (pinfunction "E_2") (pintype "passive"))
      (node (ref "R19") (pin "1") (pinfunction "A_1") (pintype "passive"))
      (node (ref "R20") (pin "1") (pinfunction "A_1") (pintype "passive"))
      (node (ref "R33") (pin "1") (pinfunction "1_1") (pintype "passive"))
      (node (ref "R36") (pin "1") (pinfunction "A_1") (pintype "passive"))
      (node (ref "R38") (pin "1") (pinfunction "A_1") (pintype "passive"))
      (node (ref "SW1") (pin "C") (pinfunction "C_C") (pintype "passive"))
      (node (ref "SW1") (pin "D") (pinfunction "1_D") (pintype "passive"))
      (node (ref "SW2") (pin "A") (pinfunction "P_A") (pintype "passive"))
      (node (ref "SW2") (pin "A'") (pinfunction "P1_A'") (pintype "passive"))
      (node (ref "U1") (pin "3") (pinfunction "P$1_3") (pintype "bidirectional"))
      (node (ref "U2") (pin "3") (pinfunction "P$1_3") (pintype "bidirectional"))
      (node (ref "U2") (pin "5") (pinfunction "P$1_5") (pintype "bidirectional"))
      (node (ref "U3") (pin "3") (pinfunction "P$1_3") (pintype "bidirectional"))
      (node (ref "U3") (pin "5") (pinfunction "P$1_5") (pintype "bidirectional"))
      (node (ref "U4") (pin "3") (pinfunction "P$1_3") (pintype "bidirectional"))
      (node (ref "U4") (pin "4") (pinfunction "P$2_4") (pintype "bidirectional"))
      (node (ref "U4") (pin "5") (pinfunction "P$1_5") (pintype "bidirectional"))
      (node (ref "U5") (pin "3") (pinfunction "P$1_3") (pintype "bidirectional"))
      (node (ref "U5") (pin "4") (pinfunction "P$2_4") (pintype "bidirectional"))
      (node (ref "U5") (pin "5") (pinfunction "P$1_5") (pintype "bidirectional"))
      (node (ref "UC1") (pin "20") (pinfunction "PB2/BOOT1_20") (pintype "bidirectional"))
      (node (ref "UC1") (pin "23") (pinfunction "VSS_1_23") (pintype "power_in"))
      (node (ref "UC1") (pin "35") (pinfunction "VSS_2_35") (pintype "power_in"))
      (node (ref "UC1") (pin "46") (pinfunction "PB9/TIM4_CH4_46") (pintype "input"))
      (node (ref "UC1") (pin "47") (pinfunction "VSS_3_47") (pintype "power_in"))
      (node (ref "UC1") (pin "8") (pinfunction "VSS_A_8") (pintype "power_in"))
    )
    (net (code "27") (name "JTCK") (class "Default")
      (node (ref "JP2") (pin "4") (pinfunction "4_4") (pintype "passive"))
      (node (ref "UC1") (pin "37") (pinfunction "PA14/JTCK/SWCLK_37") (pintype "bidirectional"))
    )
    (net (code "28") (name "JTDI") (class "Default")
      (node (ref "JP2") (pin "8") (pinfunction "8_8") (pintype "passive"))
      (node (ref "UC1") (pin "38") (pinfunction "PA15/JTDI_38") (pintype "bidirectional"))
    )
    (net (code "29") (name "JTDO") (class "Default")
      (node (ref "JP2") (pin "6") (pinfunction "6_6") (pintype "passive"))
      (node (ref "UC1") (pin "39") (pinfunction "PB3/JTDO_39") (pintype "bidirectional"))
    )
    (net (code "30") (name "JTMS") (class "Default")
      (node (ref "JP2") (pin "2") (pinfunction "2_2") (pintype "passive"))
      (node (ref "UC1") (pin "34") (pinfunction "PA13/JTMS/SWDIO_34") (pintype "bidirectional"))
    )
    (net (code "31") (name "Net-(C21-Pad1)") (class "Default")
      (node (ref "C21") (pin "1") (pinfunction "1_1") (pintype "passive"))
      (node (ref "R45") (pin "1") (pinfunction "1_1") (pintype "passive"))
      (node (ref "R46") (pin "2") (pinfunction "2_2") (pintype "passive"))
    )
    (net (code "32") (name "Net-(C24-Pad-)") (class "Default")
      (node (ref "C24") (pin "-") (pinfunction "-_-") (pintype "passive"))
      (node (ref "R50") (pin "2") (pinfunction "2_2") (pintype "passive"))
    )
    (net (code "33") (name "Net-(D1-Pad+)") (class "Default")
      (node (ref "D1") (pin "+") (pinfunction "+_+") (pintype "passive"))
      (node (ref "P1") (pin "10") (pinfunction "+12V_10") (pintype "bidirectional"))
      (node (ref "P1") (pin "9") (pinfunction "+12V_9") (pintype "bidirectional"))
    )
    (net (code "34") (name "Net-(D2-Pad-)") (class "Default")
      (node (ref "D2") (pin "-") (pinfunction "-_-") (pintype "passive"))
      (node (ref "P1") (pin "1") (pinfunction "-12V_1") (pintype "bidirectional"))
      (node (ref "P1") (pin "2") (pinfunction "-12V_2") (pintype "bidirectional"))
    )
    (net (code "35") (name "Net-(IC6-VIN)") (class "Default")
      (node (ref "C19") (pin "+") (pinfunction "+_+") (pintype "passive"))
      (node (ref "IC6") (pin "2") (pinfunction "VIN_2") (pintype "input"))
      (node (ref "R49") (pin "1") (pinfunction "1_1") (pintype "passive"))
    )
    (net (code "36") (name "Net-(J1-PadA)") (class "Default")
      (node (ref "J1") (pin "A") (pinfunction "A_A") (pintype "passive"))
      (node (ref "J4") (pin "C") (pinfunction "C_C") (pintype "passive"))
    )
    (net (code "37") (name "Net-(J1-PadC)") (class "Default")
      (node (ref "J1") (pin "C") (pinfunction "C_C") (pintype "passive"))
      (node (ref "J5") (pin "A") (pinfunction "A_A") (pintype "passive"))
    )
    (net (code "38") (name "Net-(J1-PadIN)") (class "Default")
      (node (ref "J1") (pin "IN") (pinfunction "IN_IN") (pintype "passive"))
      (node (ref "R29") (pin "1") (pinfunction "1_1") (pintype "passive"))
    )
    (net (code "39") (name "Net-(J2-PadA)") (class "Default")
      (node (ref "J2") (pin "A") (pinfunction "A_A") (pintype "passive"))
      (node (ref "R2") (pin "1") (pinfunction "1_1") (pintype "passive"))
    )
    (net (code "40") (name "Net-(J2-PadC)") (class "Default")
      (node (ref "J2") (pin "C") (pinfunction "C_C") (pintype "passive"))
      (node (ref "J6") (pin "A") (pinfunction "A_A") (pintype "passive"))
    )
    (net (code "41") (name "Net-(J2-PadIN)") (class "Default")
      (node (ref "J2") (pin "IN") (pinfunction "IN_IN") (pintype "passive"))
      (node (ref "R54") (pin "1") (pinfunction "1_1") (pintype "passive"))
    )
    (net (code "42") (name "Net-(J3-PadA)") (class "Default")
      (node (ref "J3") (pin "A") (pinfunction "A_A") (pintype "passive"))
      (node (ref "J6") (pin "C") (pinfunction "C_C") (pintype "passive"))
    )
    (net (code "43") (name "Net-(J3-PadIN)") (class "Default")
      (node (ref "J3") (pin "IN") (pinfunction "IN_IN") (pintype "passive"))
      (node (ref "R24") (pin "1") (pinfunction "1_1") (pintype "passive"))
    )
    (net (code "44") (name "Net-(J4-PadA)") (class "Default")
      (node (ref "J4") (pin "A") (pinfunction "A_A") (pintype "passive"))
      (node (ref "R1") (pin "1") (pinfunction "1_1") (pintype "passive"))
    )
    (net (code "45") (name "Net-(J4-PadIN)") (class "Default")
      (node (ref "J4") (pin "IN") (pinfunction "IN_IN") (pintype "passive"))
      (node (ref "R48") (pin "1") (pinfunction "1_1") (pintype "passive"))
    )
    (net (code "46") (name "Net-(J5-PadIN)") (class "Default")
      (node (ref "J5") (pin "IN") (pinfunction "IN_IN") (pintype "passive"))
      (node (ref "R47") (pin "1") (pinfunction "1_1") (pintype "passive"))
    )
    (net (code "47") (name "Net-(J6-PadIN)") (class "Default")
      (node (ref "J6") (pin "IN") (pinfunction "IN_IN") (pintype "passive"))
      (node (ref "R55") (pin "1") (pinfunction "1_1") (pintype "passive"))
      (node (ref "R56") (pin "1") (pinfunction "1_1") (pintype "passive"))
    )
    (net (code "48") (name "Net-(JP1-Pad2)") (class "Default")
      (node (ref "JP1") (pin "2") (pinfunction "2_2") (pintype "passive"))
      (node (ref "R1") (pin "2") (pinfunction "2_2") (pintype "passive"))
      (node (ref "R2") (pin "2") (pinfunction "2_2") (pintype "passive"))
    )
    (net (code "49") (name "Net-(Q6-B)") (class "Default")
      (node (ref "Q6") (pin "1") (pinfunction "B_1") (pintype "passive"))
      (node (ref "R29") (pin "2") (pinfunction "2_2") (pintype "passive"))
    )
    (net (code "50") (name "Net-(R20-W)") (class "Default")
      (node (ref "R20") (pin "2") (pinfunction "W_2") (pintype "passive"))
      (node (ref "R39") (pin "1") (pinfunction "1_1") (pintype "passive"))
    )
    (net (code "51") (name "Net-(R21-A)") (class "Default")
      (node (ref "C17") (pin "1") (pinfunction "1_1") (pintype "passive"))
      (node (ref "R21") (pin "1") (pinfunction "A_1") (pintype "passive"))
      (node (ref "R35") (pin "1") (pinfunction "1_1") (pintype "passive"))
      (node (ref "R40") (pin "2") (pinfunction "2_2") (pintype "passive"))
      (node (ref "R42") (pin "2") (pinfunction "2_2") (pintype "passive"))
      (node (ref "U4") (pin "2") (pinfunction "P$2_2") (pintype "bidirectional"))
    )
    (net (code "52") (name "Net-(R21-B)") (class "Default")
      (node (ref "R21") (pin "3") (pinfunction "B_3") (pintype "passive"))
      (node (ref "R52") (pin "1") (pinfunction "1_1") (pintype "passive"))
      (node (ref "U3") (pin "2") (pinfunction "P$2_2") (pintype "bidirectional"))
    )
    (net (code "53") (name "Net-(R21-W)") (class "Default")
      (node (ref "R21") (pin "2") (pinfunction "W_2") (pintype "passive"))
      (node (ref "R24") (pin "2") (pinfunction "2_2") (pintype "passive"))
    )
    (net (code "54") (name "Net-(R36-W)") (class "Default")
      (node (ref "R28") (pin "1") (pinfunction "1_1") (pintype "passive"))
      (node (ref "R36") (pin "2") (pinfunction "W_2") (pintype "passive"))
    )
    (net (code "55") (name "Net-(R37-A)") (class "Default")
      (node (ref "C13") (pin "1") (pinfunction "1_1") (pintype "passive"))
      (node (ref "R25") (pin "1") (pinfunction "1_1") (pintype "passive"))
      (node (ref "R28") (pin "2") (pinfunction "2_2") (pintype "passive"))
      (node (ref "R30") (pin "2") (pinfunction "2_2") (pintype "passive"))
      (node (ref "R37") (pin "1") (pinfunction "A_1") (pintype "passive"))
      (node (ref "U5") (pin "6") (pinfunction "P$2_6") (pintype "bidirectional"))
    )
    (net (code "56") (name "Net-(R37-B)") (class "Default")
      (node (ref "R37") (pin "3") (pinfunction "B_3") (pintype "passive"))
      (node (ref "R43") (pin "1") (pinfunction "1_1") (pintype "passive"))
      (node (ref "U2") (pin "6") (pinfunction "P$2_6") (pintype "bidirectional"))
    )
    (net (code "57") (name "Net-(R37-W)") (class "Default")
      (node (ref "R37") (pin "2") (pinfunction "W_2") (pintype "passive"))
      (node (ref "R48") (pin "2") (pinfunction "2_2") (pintype "passive"))
    )
    (net (code "58") (name "Net-(R38-W)") (class "Default")
      (node (ref "R32") (pin "1") (pinfunction "1_1") (pintype "passive"))
      (node (ref "R38") (pin "2") (pinfunction "W_2") (pintype "passive"))
    )
    (net (code "59") (name "Net-(U1A-P$2)") (class "Default")
      (node (ref "C29") (pin "1") (pinfunction "1_1") (pintype "passive"))
      (node (ref "R50") (pin "1") (pinfunction "1_1") (pintype "passive"))
      (node (ref "R56") (pin "2") (pinfunction "2_2") (pintype "passive"))
      (node (ref "U1") (pin "2") (pinfunction "P$2_2") (pintype "bidirectional"))
    )
    (net (code "60") (name "Net-(U1A-P$3)") (class "Default")
      (node (ref "C29") (pin "2") (pinfunction "2_2") (pintype "passive"))
      (node (ref "R55") (pin "2") (pinfunction "2_2") (pintype "passive"))
      (node (ref "U1") (pin "1") (pinfunction "P$3_1") (pintype "bidirectional"))
    )
    (net (code "61") (name "Net-(U1B-P$1)") (class "Default")
      (node (ref "C22") (pin "1") (pinfunction "1_1") (pintype "passive"))
      (node (ref "R46") (pin "1") (pinfunction "1_1") (pintype "passive"))
      (node (ref "U1") (pin "5") (pinfunction "P$1_5") (pintype "bidirectional"))
    )
    (net (code "62") (name "Net-(U1B-P$2)") (class "Default")
      (node (ref "C21") (pin "2") (pinfunction "2_2") (pintype "passive"))
      (node (ref "C24") (pin "+") (pinfunction "+_+") (pintype "passive"))
      (node (ref "U1") (pin "6") (pinfunction "P$2_6") (pintype "bidirectional"))
      (node (ref "U1") (pin "7") (pinfunction "P$3_7") (pintype "bidirectional"))
    )
    (net (code "63") (name "Net-(U2A-P$2)") (class "Default")
      (node (ref "R53") (pin "1") (pinfunction "1_1") (pintype "passive"))
      (node (ref "R54") (pin "2") (pinfunction "2_2") (pintype "passive"))
      (node (ref "U2") (pin "2") (pinfunction "P$2_2") (pintype "bidirectional"))
    )
    (net (code "64") (name "Net-(U2A-P$3)") (class "Default")
      (node (ref "R41") (pin "1") (pinfunction "1_1") (pintype "passive"))
      (node (ref "R53") (pin "2") (pinfunction "2_2") (pintype "passive"))
      (node (ref "U2") (pin "1") (pinfunction "P$3_1") (pintype "bidirectional"))
    )
    (net (code "65") (name "Net-(U2B-P$3)") (class "Default")
      (node (ref "R30") (pin "1") (pinfunction "1_1") (pintype "passive"))
      (node (ref "R43") (pin "2") (pinfunction "2_2") (pintype "passive"))
      (node (ref "U2") (pin "7") (pinfunction "P$3_7") (pintype "bidirectional"))
    )
    (net (code "66") (name "Net-(U3A-P$3)") (class "Default")
      (node (ref "R42") (pin "1") (pinfunction "1_1") (pintype "passive"))
      (node (ref "R52") (pin "2") (pinfunction "2_2") (pintype "passive"))
      (node (ref "U3") (pin "1") (pinfunction "P$3_1") (pintype "bidirectional"))
    )
    (net (code "67") (name "Net-(U3B-P$2)") (class "Default")
      (node (ref "R44") (pin "1") (pinfunction "1_1") (pintype "passive"))
      (node (ref "R47") (pin "2") (pinfunction "2_2") (pintype "passive"))
      (node (ref "U3") (pin "6") (pinfunction "P$2_6") (pintype "bidirectional"))
    )
    (net (code "68") (name "Net-(U3B-P$3)") (class "Default")
      (node (ref "R31") (pin "1") (pinfunction "1_1") (pintype "passive"))
      (node (ref "R44") (pin "2") (pinfunction "2_2") (pintype "passive"))
      (node (ref "U3") (pin "7") (pinfunction "P$3_7") (pintype "bidirectional"))
    )
    (net (code "69") (name "Net-(U4B-P$2)") (class "Default")
      (node (ref "C14") (pin "1") (pinfunction "1_1") (pintype "passive"))
      (node (ref "R26") (pin "1") (pinfunction "1_1") (pintype "passive"))
      (node (ref "R31") (pin "2") (pinfunction "2_2") (pintype "passive"))
      (node (ref "R32") (pin "2") (pinfunction "2_2") (pintype "passive"))
      (node (ref "U4") (pin "6") (pinfunction "P$2_6") (pintype "bidirectional"))
    )
    (net (code "70") (name "Net-(U5A-P$2)") (class "Default")
      (node (ref "C16") (pin "1") (pinfunction "1_1") (pintype "passive"))
      (node (ref "R34") (pin "1") (pinfunction "1_1") (pintype "passive"))
      (node (ref "R39") (pin "2") (pinfunction "2_2") (pintype "passive"))
      (node (ref "R41") (pin "2") (pinfunction "2_2") (pintype "passive"))
      (node (ref "U5") (pin "2") (pinfunction "P$2_2") (pintype "bidirectional"))
    )
    (net (code "71") (name "Net-(UC1-PD0-OSC_IN)") (class "Default")
      (node (ref "C9") (pin "2") (pinfunction "2_2") (pintype "passive"))
      (node (ref "Q5") (pin "2") (pinfunction "2_2") (pintype "passive"))
      (node (ref "UC1") (pin "5") (pinfunction "PD0-OSC_IN_5") (pintype "input"))
    )
    (net (code "72") (name "Net-(UC1-PD1-OSC_OUT)") (class "Default")
      (node (ref "C10") (pin "2") (pinfunction "2_2") (pintype "passive"))
      (node (ref "Q5") (pin "1") (pinfunction "1_1") (pintype "passive"))
      (node (ref "UC1") (pin "6") (pinfunction "PD1-OSC_OUT_6") (pintype "input"))
    )
    (net (code "73") (name "PARAM1_CV") (class "Default")
      (node (ref "C13") (pin "2") (pinfunction "2_2") (pintype "passive"))
      (node (ref "IC4") (pin "1") (pinfunction "CH0_1") (pintype "bidirectional"))
      (node (ref "R25") (pin "2") (pinfunction "2_2") (pintype "passive"))
      (node (ref "U5") (pin "7") (pinfunction "P$3_7") (pintype "bidirectional"))
    )
    (net (code "74") (name "PARAM2_CV") (class "Default")
      (node (ref "C14") (pin "2") (pinfunction "2_2") (pintype "passive"))
      (node (ref "IC4") (pin "2") (pinfunction "CH1_2") (pintype "bidirectional"))
      (node (ref "R26") (pin "2") (pinfunction "2_2") (pintype "passive"))
      (node (ref "U4") (pin "7") (pinfunction "P$3_7") (pintype "bidirectional"))
    )
    (net (code "75") (name "PITCH_CV") (class "Default")
      (node (ref "C16") (pin "2") (pinfunction "2_2") (pintype "passive"))
      (node (ref "IC4") (pin "3") (pinfunction "CH2_3") (pintype "bidirectional"))
      (node (ref "R34") (pin "2") (pinfunction "2_2") (pintype "passive"))
      (node (ref "U5") (pin "1") (pinfunction "P$3_1") (pintype "bidirectional"))
    )
    (net (code "76") (name "RESET") (class "Default")
      (node (ref "JP2") (pin "10") (pinfunction "10_10") (pintype "passive"))
      (node (ref "R22") (pin "1") (pinfunction "1_1") (pintype "passive"))
      (node (ref "SW2") (pin "B") (pinfunction "S_B") (pintype "passive"))
      (node (ref "SW2") (pin "B'") (pinfunction "S1_B'") (pintype "passive"))
      (node (ref "UC1") (pin "7") (pinfunction "NRST_7") (pintype "input"))
    )
    (net (code "77") (name "RX") (class "Default")
      (node (ref "JP3") (pin "4") (pinfunction "4_4") (pintype "passive"))
      (node (ref "UC1") (pin "31") (pinfunction "PA10/USART1_RX/TIM1_CH3_31") (pintype "bidirectional"))
    )
    (net (code "78") (name "TX") (class "Default")
      (node (ref "JP3") (pin "5") (pinfunction "5_5") (pintype "passive"))
      (node (ref "UC1") (pin "30") (pinfunction "PA9/USART1_TX/TIM1_CH2_30") (pintype "input"))
    )
    (net (code "79") (name "VCC") (class "Default")
      (node (ref "C1") (pin "1") (pinfunction "1_1") (pintype "passive"))
      (node (ref "C23") (pin "1") (pinfunction "1_1") (pintype "passive"))
      (node (ref "C25") (pin "+") (pinfunction "+_+") (pintype "passive"))
      (node (ref "C28") (pin "1") (pinfunction "1_1") (pintype "passive"))
      (node (ref "D1") (pin "-") (pinfunction "-_-") (pintype "passive"))
      (node (ref "JP1") (pin "1") (pinfunction "1_1") (pintype "passive"))
      (node (ref "R49") (pin "2") (pinfunction "2_2") (pintype "passive"))
      (node (ref "U1") (pin "8") (pinfunction "P$1_8") (pintype "bidirectional"))
      (node (ref "U2") (pin "8") (pinfunction "P$1_8") (pintype "bidirectional"))
      (node (ref "U3") (pin "8") (pinfunction "P$1_8") (pintype "bidirectional"))
    )
    (net (code "80") (name "VEE") (class "Default")
      (node (ref "C20") (pin "2") (pinfunction "2_2") (pintype "passive"))
      (node (ref "C27") (pin "2") (pinfunction "2_2") (pintype "passive"))
      (node (ref "C3") (pin "2") (pinfunction "2_2") (pintype "passive"))
      (node (ref "C30") (pin "-") (pinfunction "-_-") (pintype "passive"))
      (node (ref "D2") (pin "+") (pinfunction "+_+") (pintype "passive"))
      (node (ref "R51") (pin "1") (pinfunction "1_1") (pintype "passive"))
      (node (ref "U1") (pin "4") (pinfunction "P$2_4") (pintype "bidirectional"))
      (node (ref "U2") (pin "4") (pinfunction "P$2_4") (pintype "bidirectional"))
      (node (ref "U3") (pin "4") (pinfunction "P$2_4") (pintype "bidirectional"))
    )
    (net (code "81") (name "unconnected-(J1-PadNORM)") (class "Default")
      (node (ref "J1") (pin "NORM") (pinfunction "NORM_NORM") (pintype "passive"))
    )
    (net (code "82") (name "unconnected-(J2-PadNORM)") (class "Default")
      (node (ref "J2") (pin "NORM") (pinfunction "NORM_NORM") (pintype "passive"))
    )
    (net (code "83") (name "unconnected-(J3-PadNORM)") (class "Default")
      (node (ref "J3") (pin "NORM") (pinfunction "NORM_NORM") (pintype "passive"))
    )
    (net (code "84") (name "unconnected-(J4-PadNORM)") (class "Default")
      (node (ref "J4") (pin "NORM") (pinfunction "NORM_NORM") (pintype "passive"))
    )
    (net (code "85") (name "unconnected-(J5-PadNORM)") (class "Default")
      (node (ref "J5") (pin "NORM") (pinfunction "NORM_NORM") (pintype "passive"))
    )
    (net (code "86") (name "unconnected-(J6-PadNORM)") (class "Default")
      (node (ref "J6") (pin "NORM") (pinfunction "NORM_NORM") (pintype "passive"))
    )
    (net (code "87") (name "unconnected-(JP1-Pad3)") (class "Default")
      (node (ref "JP1") (pin "3") (pinfunction "3_3") (pintype "passive"))
    )
    (net (code "88") (name "unconnected-(JP2-Pad7)") (class "Default")
      (node (ref "JP2") (pin "7") (pinfunction "7_7") (pintype "passive"))
    )
    (net (code "89") (name "unconnected-(JP3-Pad2)") (class "Default")
      (node (ref "JP3") (pin "2") (pinfunction "2_2") (pintype "passive"))
    )
    (net (code "90") (name "unconnected-(JP3-Pad3)") (class "Default")
      (node (ref "JP3") (pin "3") (pinfunction "3_3") (pintype "passive"))
    )
    (net (code "91") (name "unconnected-(JP3-Pad6)") (class "Default")
      (node (ref "JP3") (pin "6") (pinfunction "6_6") (pintype "passive"))
    )
    (net (code "92") (name "unconnected-(UC1-PA0_WKUP{slash}USART2_CTS{slash}ADC12_IN0{slash}TIM2_CH1_ETR-Pad10)") (class "Default")
      (node (ref "UC1") (pin "10") (pinfunction "PA0_WKUP/USART2_CTS/ADC12_IN0/TIM2_CH1_ETR_10") (pintype "bidirectional"))
    )
    (net (code "93") (name "unconnected-(UC1-PA1{slash}USART2_RTS{slash}ADC12_IN1{slash}TIM2_CH2-Pad11)") (class "Default")
      (node (ref "UC1") (pin "11") (pinfunction "PA1/USART2_RTS/ADC12_IN1/TIM2_CH2_11") (pintype "bidirectional"))
    )
    (net (code "94") (name "unconnected-(UC1-PA2{slash}USART2_TX{slash}ADC12_IN2{slash}TIM2_CH3-Pad12)") (class "Default")
      (node (ref "UC1") (pin "12") (pinfunction "PA2/USART2_TX/ADC12_IN2/TIM2_CH3_12") (pintype "bidirectional"))
    )
    (net (code "95") (name "unconnected-(UC1-PA8{slash}USART1_CK{slash}TIM1_CH1{slash}MCO-Pad29)") (class "Default")
      (node (ref "UC1") (pin "29") (pinfunction "PA8/USART1_CK/TIM1_CH1/MCO_29") (pintype "bidirectional"))
    )
    (net (code "96") (name "unconnected-(UC1-PA11{slash}USART1_CTS{slash}CAN_RX{slash}TIM1_CH4{slash}USBDM-Pad32)") (class "Default")
      (node (ref "UC1") (pin "32") (pinfunction "PA11/USART1_CTS/CAN_RX/TIM1_CH4/USBDM_32") (pintype "bidirectional"))
    )
    (net (code "97") (name "unconnected-(UC1-PA12{slash}USART1_RTS{slash}CAN_TX{slash}TIM1_ETR{slash}USBDP-Pad33)") (class "Default")
      (node (ref "UC1") (pin "33") (pinfunction "PA12/USART1_RTS/CAN_TX/TIM1_ETR/USBDP_33") (pintype "bidirectional"))
    )
    (net (code "98") (name "unconnected-(UC1-PB4{slash}NJTRST-Pad40)") (class "Default")
      (node (ref "UC1") (pin "40") (pinfunction "PB4/NJTRST_40") (pintype "bidirectional"))
    )
    (net (code "99") (name "unconnected-(UC1-PB14{slash}SPI2_MISO{slash}USART3_RTS{slash}TIM1_CH2N-Pad27)") (class "Default")
      (node (ref "UC1") (pin "27") (pinfunction "PB14/SPI2_MISO/USART3_RTS/TIM1_CH2N_27") (pintype "input"))
    )
  )
)
